# tc_breakout.net
KiCad netlist of a schematic drawn in EAGLE
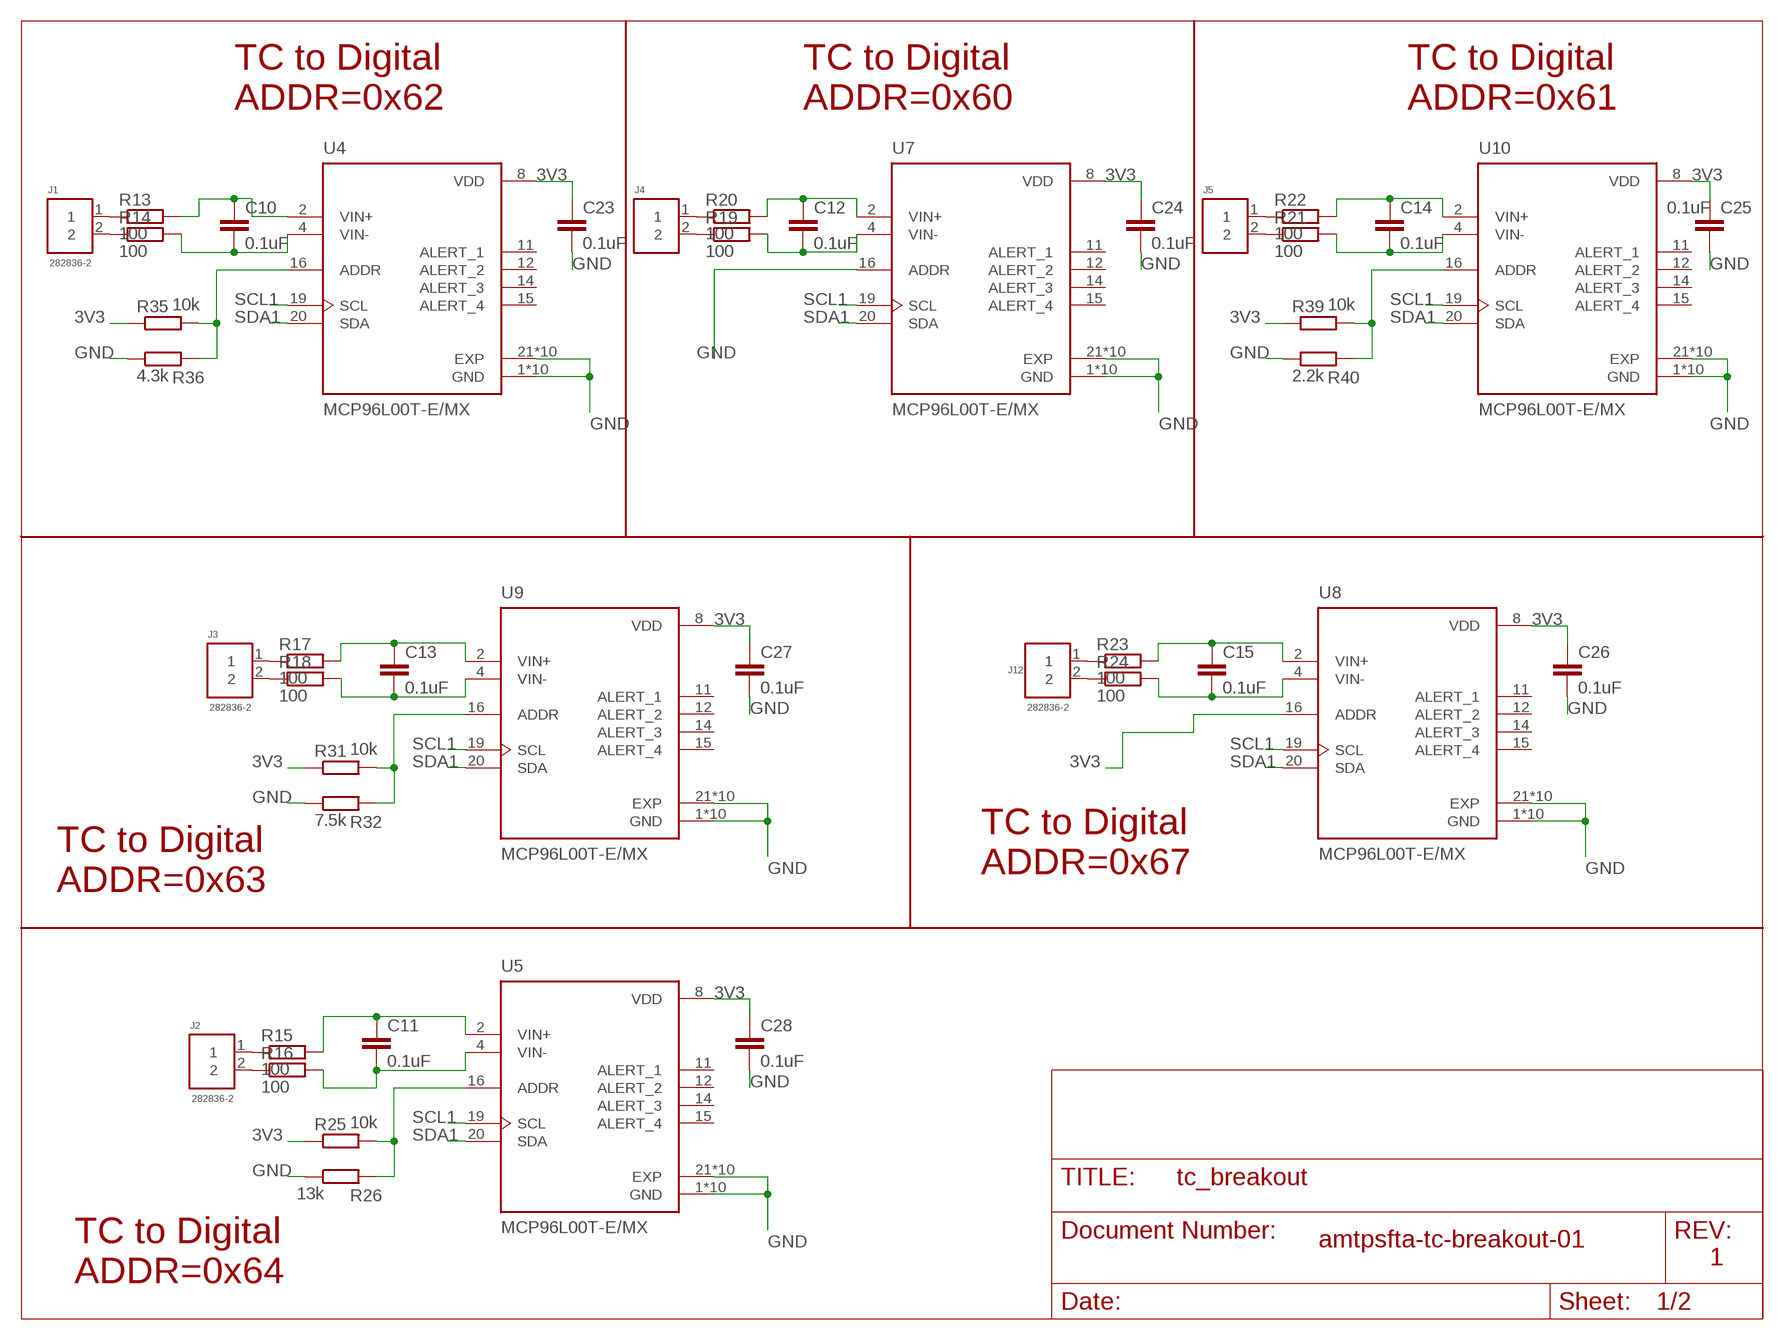
[diagram p0: schematic, sheet 1]
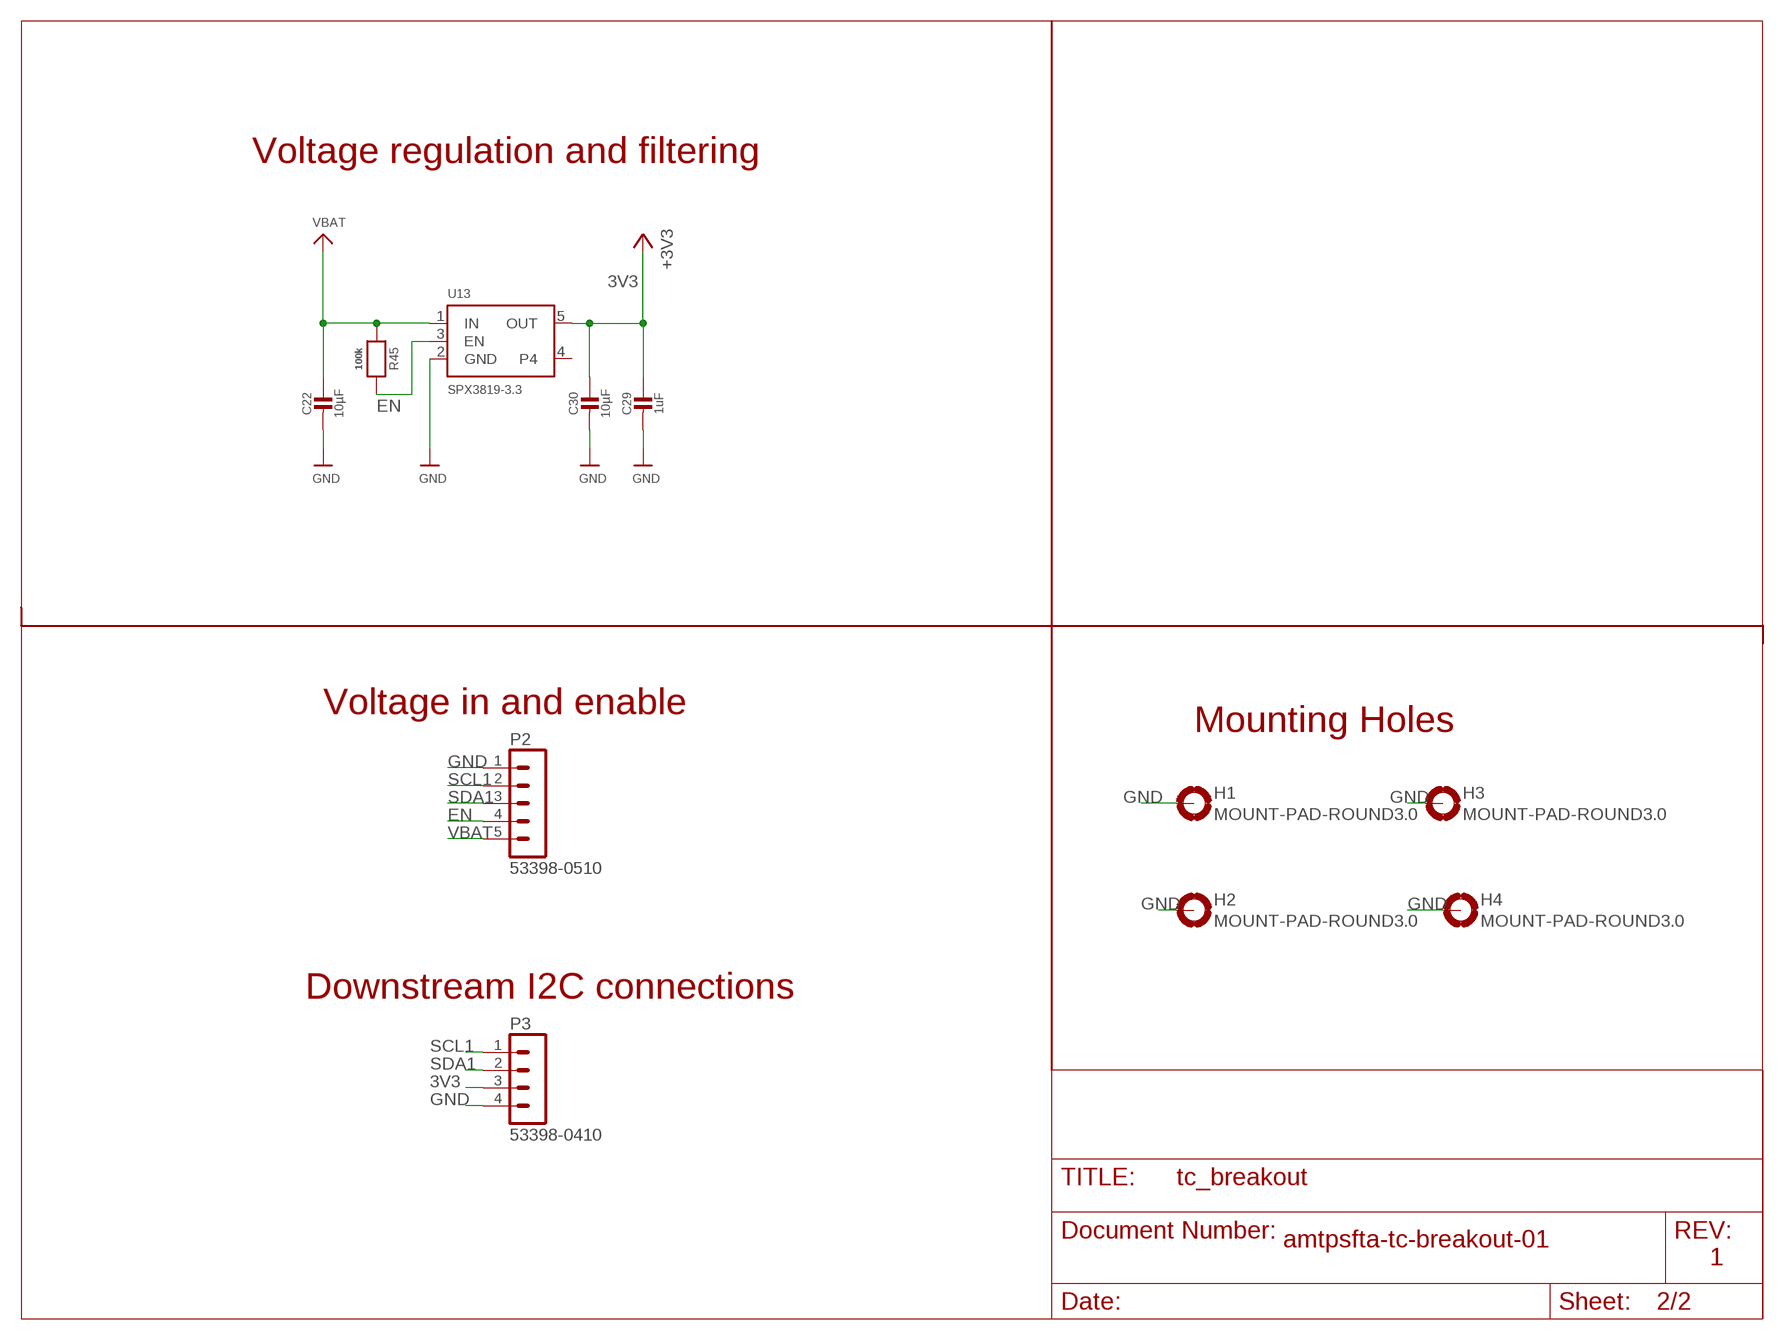
[diagram p1: schematic, sheet 2]

(export (version "E")
  (design (tool "Eeschema 10.0.6"))
  (components
    (comp (ref "C22")
      (value "10µF")
      (footprint "eagle-import:0805-NO")
      (libsource (lib "eagle-import") (part "CAP_CERAMIC0805-NOOUTLINE"))
    )
    (comp (ref "C29")
      (value "1uF")
      (footprint "eagle-import:0603-NO")
      (libsource (lib "eagle-import") (part "CAP_CERAMIC0603_NO"))
    )
    (comp (ref "C30")
      (value "10µF")
      (footprint "eagle-import:0805-NO")
      (libsource (lib "eagle-import") (part "CAP_CERAMIC0805-NOOUTLINE"))
    )
    (comp (ref "H1")
      (value "MOUNT-PAD-ROUND3.0")
      (footprint "eagle-import:3,0-PAD")
      (libsource (lib "eagle-import") (part "MOUNT-PAD-ROUND3.0"))
    )
    (comp (ref "H2")
      (value "MOUNT-PAD-ROUND3.0")
      (footprint "eagle-import:3,0-PAD")
      (libsource (lib "eagle-import") (part "MOUNT-PAD-ROUND3.0"))
    )
    (comp (ref "H3")
      (value "MOUNT-PAD-ROUND3.0")
      (footprint "eagle-import:3,0-PAD")
      (libsource (lib "eagle-import") (part "MOUNT-PAD-ROUND3.0"))
    )
    (comp (ref "H4")
      (value "MOUNT-PAD-ROUND3.0")
      (footprint "eagle-import:3,0-PAD")
      (libsource (lib "eagle-import") (part "MOUNT-PAD-ROUND3.0"))
    )
    (comp (ref "P2")
      (value "53398-0510")
      (footprint "eagle-import:53398-0510")
      (libsource (lib "eagle-import") (part "53398-0510"))
    )
    (comp (ref "P3")
      (value "53398-0410")
      (footprint "eagle-import:53398-0410")
      (libsource (lib "eagle-import") (part "53398-0410"))
    )
    (comp (ref "R45")
      (value "100k")
      (footprint "eagle-import:0603-NO")
      (libsource (lib "eagle-import") (part "RESISTOR_0603_NOOUT"))
    )
    (comp (ref "U13")
      (value "SPX3819-3.3")
      (footprint "eagle-import:SOT23-5")
      (libsource (lib "eagle-import") (part "VREG_SOT23-5"))
    )
    (comp (ref "C10")
      (value "0.1uF")
      (footprint "eagle-import:C0603")
      (libsource (lib "eagle-import") (part "C-EUC0603"))
    )
    (comp (ref "C11")
      (value "0.1uF")
      (footprint "eagle-import:C0603")
      (libsource (lib "eagle-import") (part "C-EUC0603"))
    )
    (comp (ref "C12")
      (value "0.1uF")
      (footprint "eagle-import:C0603")
      (libsource (lib "eagle-import") (part "C-EUC0603"))
    )
    (comp (ref "C13")
      (value "0.1uF")
      (footprint "eagle-import:C0603")
      (libsource (lib "eagle-import") (part "C-EUC0603"))
    )
    (comp (ref "C14")
      (value "0.1uF")
      (footprint "eagle-import:C0603")
      (libsource (lib "eagle-import") (part "C-EUC0603"))
    )
    (comp (ref "C15")
      (value "0.1uF")
      (footprint "eagle-import:C0603")
      (libsource (lib "eagle-import") (part "C-EUC0603"))
    )
    (comp (ref "C23")
      (value "0.1uF")
      (footprint "eagle-import:C0603")
      (libsource (lib "eagle-import") (part "C-EUC0603"))
    )
    (comp (ref "C24")
      (value "0.1uF")
      (footprint "eagle-import:C0603")
      (libsource (lib "eagle-import") (part "C-EUC0603"))
    )
    (comp (ref "C25")
      (value "0.1uF")
      (footprint "eagle-import:C0603")
      (libsource (lib "eagle-import") (part "C-EUC0603"))
    )
    (comp (ref "C26")
      (value "0.1uF")
      (footprint "eagle-import:C0603")
      (libsource (lib "eagle-import") (part "C-EUC0603"))
    )
    (comp (ref "C27")
      (value "0.1uF")
      (footprint "eagle-import:C0603")
      (libsource (lib "eagle-import") (part "C-EUC0603"))
    )
    (comp (ref "C28")
      (value "0.1uF")
      (footprint "eagle-import:C0603")
      (libsource (lib "eagle-import") (part "C-EUC0603"))
    )
    (comp (ref "J1")
      (value "282836-2")
      (footprint "eagle-import:CONN_282836-2")
      (fields (field (name "MF") "TE Connectivity") (field (name "MP") "2828362"))
      (libsource (lib "eagle-import") (part "282836-2"))
    )
    (comp (ref "J2")
      (value "282836-2")
      (footprint "eagle-import:CONN_282836-2")
      (fields (field (name "MF") "TE Connectivity") (field (name "MP") "2828362"))
      (libsource (lib "eagle-import") (part "282836-2"))
    )
    (comp (ref "J3")
      (value "282836-2")
      (footprint "eagle-import:CONN_282836-2")
      (fields (field (name "MF") "TE Connectivity") (field (name "MP") "2828362"))
      (libsource (lib "eagle-import") (part "282836-2"))
    )
    (comp (ref "J4")
      (value "282836-2")
      (footprint "eagle-import:CONN_282836-2")
      (fields (field (name "MF") "TE Connectivity") (field (name "MP") "2828362"))
      (libsource (lib "eagle-import") (part "282836-2"))
    )
    (comp (ref "J5")
      (value "282836-2")
      (footprint "eagle-import:CONN_282836-2")
      (fields (field (name "MF") "TE Connectivity") (field (name "MP") "2828362"))
      (libsource (lib "eagle-import") (part "282836-2"))
    )
    (comp (ref "J12")
      (value "282836-2")
      (footprint "eagle-import:CONN_282836-2")
      (fields (field (name "MF") "TE Connectivity") (field (name "MP") "2828362"))
      (libsource (lib "eagle-import") (part "282836-2"))
    )
    (comp (ref "R13")
      (value "100")
      (footprint "eagle-import:R0603")
      (libsource (lib "eagle-import") (part "R-EU_R0603"))
    )
    (comp (ref "R14")
      (value "100")
      (footprint "eagle-import:R0603")
      (libsource (lib "eagle-import") (part "R-EU_R0603"))
    )
    (comp (ref "R15")
      (value "100")
      (footprint "eagle-import:R0603")
      (libsource (lib "eagle-import") (part "R-EU_R0603"))
    )
    (comp (ref "R16")
      (value "100")
      (footprint "eagle-import:R0603")
      (libsource (lib "eagle-import") (part "R-EU_R0603"))
    )
    (comp (ref "R17")
      (value "100")
      (footprint "eagle-import:R0603")
      (libsource (lib "eagle-import") (part "R-EU_R0603"))
    )
    (comp (ref "R18")
      (value "100")
      (footprint "eagle-import:R0603")
      (libsource (lib "eagle-import") (part "R-EU_R0603"))
    )
    (comp (ref "R19")
      (value "100")
      (footprint "eagle-import:R0603")
      (libsource (lib "eagle-import") (part "R-EU_R0603"))
    )
    (comp (ref "R20")
      (value "100")
      (footprint "eagle-import:R0603")
      (libsource (lib "eagle-import") (part "R-EU_R0603"))
    )
    (comp (ref "R21")
      (value "100")
      (footprint "eagle-import:R0603")
      (libsource (lib "eagle-import") (part "R-EU_R0603"))
    )
    (comp (ref "R22")
      (value "100")
      (footprint "eagle-import:R0603")
      (libsource (lib "eagle-import") (part "R-EU_R0603"))
    )
    (comp (ref "R23")
      (value "100")
      (footprint "eagle-import:R0603")
      (libsource (lib "eagle-import") (part "R-EU_R0603"))
    )
    (comp (ref "R24")
      (value "100")
      (footprint "eagle-import:R0603")
      (libsource (lib "eagle-import") (part "R-EU_R0603"))
    )
    (comp (ref "R25")
      (value "10k")
      (footprint "eagle-import:R0603")
      (libsource (lib "eagle-import") (part "R-EU_R0603"))
    )
    (comp (ref "R26")
      (value "13k")
      (footprint "eagle-import:R0603")
      (libsource (lib "eagle-import") (part "R-EU_R0603"))
    )
    (comp (ref "R31")
      (value "10k")
      (footprint "eagle-import:R0603")
      (libsource (lib "eagle-import") (part "R-EU_R0603"))
    )
    (comp (ref "R32")
      (value "7.5k")
      (footprint "eagle-import:R0603")
      (libsource (lib "eagle-import") (part "R-EU_R0603"))
    )
    (comp (ref "R35")
      (value "10k")
      (footprint "eagle-import:R0603")
      (libsource (lib "eagle-import") (part "R-EU_R0603"))
    )
    (comp (ref "R36")
      (value "4.3k")
      (footprint "eagle-import:R0603")
      (libsource (lib "eagle-import") (part "R-EU_R0603"))
    )
    (comp (ref "R39")
      (value "10k")
      (footprint "eagle-import:R0603")
      (libsource (lib "eagle-import") (part "R-EU_R0603"))
    )
    (comp (ref "R40")
      (value "2.2k")
      (footprint "eagle-import:R0603")
      (libsource (lib "eagle-import") (part "R-EU_R0603"))
    )
    (comp (ref "U4")
      (value "MCP96L00T-E/MX")
      (footprint "eagle-import:QFN65P500X500X100-21N_MCP96L00T-E_MX")
      (fields
        (field (name "DIGI-KEY_PART_NUMBER") "MCP96L00T-E/MXCT-ND")
        (field (name "MF") "Microchip Technology")
      )
      (libsource (lib "eagle-import") (part "MCP96L00T-E/MX"))
    )
    (comp (ref "U5")
      (value "MCP96L00T-E/MX")
      (footprint "eagle-import:QFN65P500X500X100-21N_MCP96L00T-E_MX")
      (fields
        (field (name "DIGI-KEY_PART_NUMBER") "MCP96L00T-E/MXCT-ND")
        (field (name "MF") "Microchip Technology")
      )
      (libsource (lib "eagle-import") (part "MCP96L00T-E/MX"))
    )
    (comp (ref "U7")
      (value "MCP96L00T-E/MX")
      (footprint "eagle-import:QFN65P500X500X100-21N_MCP96L00T-E_MX")
      (fields
        (field (name "DIGI-KEY_PART_NUMBER") "MCP96L00T-E/MXCT-ND")
        (field (name "MF") "Microchip Technology")
      )
      (libsource (lib "eagle-import") (part "MCP96L00T-E/MX"))
    )
    (comp (ref "U8")
      (value "MCP96L00T-E/MX")
      (footprint "eagle-import:QFN65P500X500X100-21N_MCP96L00T-E_MX")
      (fields
        (field (name "DIGI-KEY_PART_NUMBER") "MCP96L00T-E/MXCT-ND")
        (field (name "MF") "Microchip Technology")
      )
      (libsource (lib "eagle-import") (part "MCP96L00T-E/MX"))
    )
    (comp (ref "U9")
      (value "MCP96L00T-E/MX")
      (footprint "eagle-import:QFN65P500X500X100-21N_MCP96L00T-E_MX")
      (fields
        (field (name "DIGI-KEY_PART_NUMBER") "MCP96L00T-E/MXCT-ND")
        (field (name "MF") "Microchip Technology")
      )
      (libsource (lib "eagle-import") (part "MCP96L00T-E/MX"))
    )
    (comp (ref "U10")
      (value "MCP96L00T-E/MX")
      (footprint "eagle-import:QFN65P500X500X100-21N_MCP96L00T-E_MX")
      (fields
        (field (name "DIGI-KEY_PART_NUMBER") "MCP96L00T-E/MXCT-ND")
        (field (name "MF") "Microchip Technology")
      )
      (libsource (lib "eagle-import") (part "MCP96L00T-E/MX"))
    )
  )
  (nets
    (net (code "1") (name "3V3") (class "Default")
      (node (ref "C23") (pin "1") (pinfunction "1_1") (pintype "passive"))
      (node (ref "C24") (pin "1") (pinfunction "1_1") (pintype "passive"))
      (node (ref "C25") (pin "1") (pinfunction "1_1") (pintype "passive"))
      (node (ref "C26") (pin "1") (pinfunction "1_1") (pintype "passive"))
      (node (ref "C27") (pin "1") (pinfunction "1_1") (pintype "passive"))
      (node (ref "C28") (pin "1") (pinfunction "1_1") (pintype "passive"))
      (node (ref "C29") (pin "1") (pinfunction "1_1") (pintype "passive"))
      (node (ref "C30") (pin "1") (pinfunction "1_1") (pintype "passive"))
      (node (ref "P3") (pin "3") (pinfunction "3_3") (pintype "passive"))
      (node (ref "R25") (pin "1") (pinfunction "1_1") (pintype "passive"))
      (node (ref "R31") (pin "1") (pinfunction "1_1") (pintype "passive"))
      (node (ref "R35") (pin "1") (pinfunction "1_1") (pintype "passive"))
      (node (ref "R39") (pin "1") (pinfunction "1_1") (pintype "passive"))
      (node (ref "U10") (pin "8") (pinfunction "VDD_8") (pintype "power_in"))
      (node (ref "U13") (pin "5") (pinfunction "OUT_5") (pintype "power_in"))
      (node (ref "U4") (pin "8") (pinfunction "VDD_8") (pintype "power_in"))
      (node (ref "U5") (pin "8") (pinfunction "VDD_8") (pintype "power_in"))
      (node (ref "U7") (pin "8") (pinfunction "VDD_8") (pintype "power_in"))
      (node (ref "U8") (pin "16") (pinfunction "ADDR_16") (pintype "input"))
      (node (ref "U8") (pin "8") (pinfunction "VDD_8") (pintype "power_in"))
      (node (ref "U9") (pin "8") (pinfunction "VDD_8") (pintype "power_in"))
    )
    (net (code "2") (name "EN") (class "Default")
      (node (ref "P2") (pin "4") (pinfunction "4_4") (pintype "passive"))
      (node (ref "R45") (pin "2") (pinfunction "2_2") (pintype "passive"))
      (node (ref "U13") (pin "3") (pinfunction "EN_3") (pintype "input"))
    )
    (net (code "3") (name "GND") (class "Default")
      (node (ref "C22") (pin "2") (pinfunction "2_2") (pintype "passive"))
      (node (ref "C23") (pin "2") (pinfunction "2_2") (pintype "passive"))
      (node (ref "C24") (pin "2") (pinfunction "2_2") (pintype "passive"))
      (node (ref "C25") (pin "2") (pinfunction "2_2") (pintype "passive"))
      (node (ref "C26") (pin "2") (pinfunction "2_2") (pintype "passive"))
      (node (ref "C27") (pin "2") (pinfunction "2_2") (pintype "passive"))
      (node (ref "C28") (pin "2") (pinfunction "2_2") (pintype "passive"))
      (node (ref "C29") (pin "2") (pinfunction "2_2") (pintype "passive"))
      (node (ref "C30") (pin "2") (pinfunction "2_2") (pintype "passive"))
      (node (ref "H1") (pin "B3,0") (pinfunction "MOUNT_B3,0") (pintype "passive"))
      (node (ref "H2") (pin "B3,0") (pinfunction "MOUNT_B3,0") (pintype "passive"))
      (node (ref "H3") (pin "B3,0") (pinfunction "MOUNT_B3,0") (pintype "passive"))
      (node (ref "H4") (pin "B3,0") (pinfunction "MOUNT_B3,0") (pintype "passive"))
      (node (ref "P2") (pin "1") (pinfunction "1_1") (pintype "passive"))
      (node (ref "P3") (pin "4") (pinfunction "4_4") (pintype "passive"))
      (node (ref "R26") (pin "1") (pinfunction "1_1") (pintype "passive"))
      (node (ref "R32") (pin "1") (pinfunction "1_1") (pintype "passive"))
      (node (ref "R36") (pin "1") (pinfunction "1_1") (pintype "passive"))
      (node (ref "R40") (pin "1") (pinfunction "1_1") (pintype "passive"))
      (node (ref "U10") (pin "1") (pinfunction "GND_1") (pintype "power_in"))
      (node (ref "U10") (pin "10") (pinfunction "GND_10") (pintype "power_in"))
      (node (ref "U10") (pin "13") (pinfunction "GND_13") (pintype "power_in"))
      (node (ref "U10") (pin "17") (pinfunction "GND_17") (pintype "power_in"))
      (node (ref "U10") (pin "18") (pinfunction "GND_18") (pintype "power_in"))
      (node (ref "U10") (pin "21") (pinfunction "EXP_21") (pintype "power_in"))
      (node (ref "U10") (pin "22") (pinfunction "EXP_22") (pintype "power_in"))
      (node (ref "U10") (pin "23") (pinfunction "EXP_23") (pintype "power_in"))
      (node (ref "U10") (pin "24") (pinfunction "EXP_24") (pintype "power_in"))
      (node (ref "U10") (pin "25") (pinfunction "EXP_25") (pintype "power_in"))
      (node (ref "U10") (pin "26") (pinfunction "EXP_26") (pintype "power_in"))
      (node (ref "U10") (pin "27") (pinfunction "EXP_27") (pintype "power_in"))
      (node (ref "U10") (pin "28") (pinfunction "EXP_28") (pintype "power_in"))
      (node (ref "U10") (pin "29") (pinfunction "EXP_29") (pintype "power_in"))
      (node (ref "U10") (pin "3") (pinfunction "GND_3") (pintype "power_in"))
      (node (ref "U10") (pin "30") (pinfunction "EXP_30") (pintype "power_in"))
      (node (ref "U10") (pin "5") (pinfunction "GND_5") (pintype "power_in"))
      (node (ref "U10") (pin "6") (pinfunction "GND_6") (pintype "power_in"))
      (node (ref "U10") (pin "7") (pinfunction "GND_7") (pintype "power_in"))
      (node (ref "U10") (pin "9") (pinfunction "GND_9") (pintype "power_in"))
      (node (ref "U13") (pin "2") (pinfunction "GND_2") (pintype "power_in"))
      (node (ref "U4") (pin "1") (pinfunction "GND_1") (pintype "power_in"))
      (node (ref "U4") (pin "10") (pinfunction "GND_10") (pintype "power_in"))
      (node (ref "U4") (pin "13") (pinfunction "GND_13") (pintype "power_in"))
      (node (ref "U4") (pin "17") (pinfunction "GND_17") (pintype "power_in"))
      (node (ref "U4") (pin "18") (pinfunction "GND_18") (pintype "power_in"))
      (node (ref "U4") (pin "21") (pinfunction "EXP_21") (pintype "power_in"))
      (node (ref "U4") (pin "22") (pinfunction "EXP_22") (pintype "power_in"))
      (node (ref "U4") (pin "23") (pinfunction "EXP_23") (pintype "power_in"))
      (node (ref "U4") (pin "24") (pinfunction "EXP_24") (pintype "power_in"))
      (node (ref "U4") (pin "25") (pinfunction "EXP_25") (pintype "power_in"))
      (node (ref "U4") (pin "26") (pinfunction "EXP_26") (pintype "power_in"))
      (node (ref "U4") (pin "27") (pinfunction "EXP_27") (pintype "power_in"))
      (node (ref "U4") (pin "28") (pinfunction "EXP_28") (pintype "power_in"))
      (node (ref "U4") (pin "29") (pinfunction "EXP_29") (pintype "power_in"))
      (node (ref "U4") (pin "3") (pinfunction "GND_3") (pintype "power_in"))
      (node (ref "U4") (pin "30") (pinfunction "EXP_30") (pintype "power_in"))
      (node (ref "U4") (pin "5") (pinfunction "GND_5") (pintype "power_in"))
      (node (ref "U4") (pin "6") (pinfunction "GND_6") (pintype "power_in"))
      (node (ref "U4") (pin "7") (pinfunction "GND_7") (pintype "power_in"))
      (node (ref "U4") (pin "9") (pinfunction "GND_9") (pintype "power_in"))
      (node (ref "U5") (pin "1") (pinfunction "GND_1") (pintype "power_in"))
      (node (ref "U5") (pin "10") (pinfunction "GND_10") (pintype "power_in"))
      (node (ref "U5") (pin "13") (pinfunction "GND_13") (pintype "power_in"))
      (node (ref "U5") (pin "17") (pinfunction "GND_17") (pintype "power_in"))
      (node (ref "U5") (pin "18") (pinfunction "GND_18") (pintype "power_in"))
      (node (ref "U5") (pin "21") (pinfunction "EXP_21") (pintype "power_in"))
      (node (ref "U5") (pin "22") (pinfunction "EXP_22") (pintype "power_in"))
      (node (ref "U5") (pin "23") (pinfunction "EXP_23") (pintype "power_in"))
      (node (ref "U5") (pin "24") (pinfunction "EXP_24") (pintype "power_in"))
      (node (ref "U5") (pin "25") (pinfunction "EXP_25") (pintype "power_in"))
      (node (ref "U5") (pin "26") (pinfunction "EXP_26") (pintype "power_in"))
      (node (ref "U5") (pin "27") (pinfunction "EXP_27") (pintype "power_in"))
      (node (ref "U5") (pin "28") (pinfunction "EXP_28") (pintype "power_in"))
      (node (ref "U5") (pin "29") (pinfunction "EXP_29") (pintype "power_in"))
      (node (ref "U5") (pin "3") (pinfunction "GND_3") (pintype "power_in"))
      (node (ref "U5") (pin "30") (pinfunction "EXP_30") (pintype "power_in"))
      (node (ref "U5") (pin "5") (pinfunction "GND_5") (pintype "power_in"))
      (node (ref "U5") (pin "6") (pinfunction "GND_6") (pintype "power_in"))
      (node (ref "U5") (pin "7") (pinfunction "GND_7") (pintype "power_in"))
      (node (ref "U5") (pin "9") (pinfunction "GND_9") (pintype "power_in"))
      (node (ref "U7") (pin "1") (pinfunction "GND_1") (pintype "power_in"))
      (node (ref "U7") (pin "10") (pinfunction "GND_10") (pintype "power_in"))
      (node (ref "U7") (pin "13") (pinfunction "GND_13") (pintype "power_in"))
      (node (ref "U7") (pin "16") (pinfunction "ADDR_16") (pintype "input"))
      (node (ref "U7") (pin "17") (pinfunction "GND_17") (pintype "power_in"))
      (node (ref "U7") (pin "18") (pinfunction "GND_18") (pintype "power_in"))
      (node (ref "U7") (pin "21") (pinfunction "EXP_21") (pintype "power_in"))
      (node (ref "U7") (pin "22") (pinfunction "EXP_22") (pintype "power_in"))
      (node (ref "U7") (pin "23") (pinfunction "EXP_23") (pintype "power_in"))
      (node (ref "U7") (pin "24") (pinfunction "EXP_24") (pintype "power_in"))
      (node (ref "U7") (pin "25") (pinfunction "EXP_25") (pintype "power_in"))
      (node (ref "U7") (pin "26") (pinfunction "EXP_26") (pintype "power_in"))
      (node (ref "U7") (pin "27") (pinfunction "EXP_27") (pintype "power_in"))
      (node (ref "U7") (pin "28") (pinfunction "EXP_28") (pintype "power_in"))
      (node (ref "U7") (pin "29") (pinfunction "EXP_29") (pintype "power_in"))
      (node (ref "U7") (pin "3") (pinfunction "GND_3") (pintype "power_in"))
      (node (ref "U7") (pin "30") (pinfunction "EXP_30") (pintype "power_in"))
      (node (ref "U7") (pin "5") (pinfunction "GND_5") (pintype "power_in"))
      (node (ref "U7") (pin "6") (pinfunction "GND_6") (pintype "power_in"))
      (node (ref "U7") (pin "7") (pinfunction "GND_7") (pintype "power_in"))
      (node (ref "U7") (pin "9") (pinfunction "GND_9") (pintype "power_in"))
      (node (ref "U8") (pin "1") (pinfunction "GND_1") (pintype "power_in"))
      (node (ref "U8") (pin "10") (pinfunction "GND_10") (pintype "power_in"))
      (node (ref "U8") (pin "13") (pinfunction "GND_13") (pintype "power_in"))
      (node (ref "U8") (pin "17") (pinfunction "GND_17") (pintype "power_in"))
      (node (ref "U8") (pin "18") (pinfunction "GND_18") (pintype "power_in"))
      (node (ref "U8") (pin "21") (pinfunction "EXP_21") (pintype "power_in"))
      (node (ref "U8") (pin "22") (pinfunction "EXP_22") (pintype "power_in"))
      (node (ref "U8") (pin "23") (pinfunction "EXP_23") (pintype "power_in"))
      (node (ref "U8") (pin "24") (pinfunction "EXP_24") (pintype "power_in"))
      (node (ref "U8") (pin "25") (pinfunction "EXP_25") (pintype "power_in"))
      (node (ref "U8") (pin "26") (pinfunction "EXP_26") (pintype "power_in"))
      (node (ref "U8") (pin "27") (pinfunction "EXP_27") (pintype "power_in"))
      (node (ref "U8") (pin "28") (pinfunction "EXP_28") (pintype "power_in"))
      (node (ref "U8") (pin "29") (pinfunction "EXP_29") (pintype "power_in"))
      (node (ref "U8") (pin "3") (pinfunction "GND_3") (pintype "power_in"))
      (node (ref "U8") (pin "30") (pinfunction "EXP_30") (pintype "power_in"))
      (node (ref "U8") (pin "5") (pinfunction "GND_5") (pintype "power_in"))
      (node (ref "U8") (pin "6") (pinfunction "GND_6") (pintype "power_in"))
      (node (ref "U8") (pin "7") (pinfunction "GND_7") (pintype "power_in"))
      (node (ref "U8") (pin "9") (pinfunction "GND_9") (pintype "power_in"))
      (node (ref "U9") (pin "1") (pinfunction "GND_1") (pintype "power_in"))
      (node (ref "U9") (pin "10") (pinfunction "GND_10") (pintype "power_in"))
      (node (ref "U9") (pin "13") (pinfunction "GND_13") (pintype "power_in"))
      (node (ref "U9") (pin "17") (pinfunction "GND_17") (pintype "power_in"))
      (node (ref "U9") (pin "18") (pinfunction "GND_18") (pintype "power_in"))
      (node (ref "U9") (pin "21") (pinfunction "EXP_21") (pintype "power_in"))
      (node (ref "U9") (pin "22") (pinfunction "EXP_22") (pintype "power_in"))
      (node (ref "U9") (pin "23") (pinfunction "EXP_23") (pintype "power_in"))
      (node (ref "U9") (pin "24") (pinfunction "EXP_24") (pintype "power_in"))
      (node (ref "U9") (pin "25") (pinfunction "EXP_25") (pintype "power_in"))
      (node (ref "U9") (pin "26") (pinfunction "EXP_26") (pintype "power_in"))
      (node (ref "U9") (pin "27") (pinfunction "EXP_27") (pintype "power_in"))
      (node (ref "U9") (pin "28") (pinfunction "EXP_28") (pintype "power_in"))
      (node (ref "U9") (pin "29") (pinfunction "EXP_29") (pintype "power_in"))
      (node (ref "U9") (pin "3") (pinfunction "GND_3") (pintype "power_in"))
      (node (ref "U9") (pin "30") (pinfunction "EXP_30") (pintype "power_in"))
      (node (ref "U9") (pin "5") (pinfunction "GND_5") (pintype "power_in"))
      (node (ref "U9") (pin "6") (pinfunction "GND_6") (pintype "power_in"))
      (node (ref "U9") (pin "7") (pinfunction "GND_7") (pintype "power_in"))
      (node (ref "U9") (pin "9") (pinfunction "GND_9") (pintype "power_in"))
    )
    (net (code "4") (name "Net-(J1-Pad1)") (class "Default")
      (node (ref "J1") (pin "1") (pinfunction "1_1") (pintype "passive"))
      (node (ref "R13") (pin "1") (pinfunction "1_1") (pintype "passive"))
    )
    (net (code "5") (name "Net-(J1-Pad2)") (class "Default")
      (node (ref "J1") (pin "2") (pinfunction "2_2") (pintype "passive"))
      (node (ref "R14") (pin "1") (pinfunction "1_1") (pintype "passive"))
    )
    (net (code "6") (name "Net-(J2-Pad1)") (class "Default")
      (node (ref "J2") (pin "1") (pinfunction "1_1") (pintype "passive"))
      (node (ref "R15") (pin "1") (pinfunction "1_1") (pintype "passive"))
    )
    (net (code "7") (name "Net-(J2-Pad2)") (class "Default")
      (node (ref "J2") (pin "2") (pinfunction "2_2") (pintype "passive"))
      (node (ref "R16") (pin "1") (pinfunction "1_1") (pintype "passive"))
    )
    (net (code "8") (name "Net-(J3-Pad1)") (class "Default")
      (node (ref "J3") (pin "1") (pinfunction "1_1") (pintype "passive"))
      (node (ref "R17") (pin "1") (pinfunction "1_1") (pintype "passive"))
    )
    (net (code "9") (name "Net-(J3-Pad2)") (class "Default")
      (node (ref "J3") (pin "2") (pinfunction "2_2") (pintype "passive"))
      (node (ref "R18") (pin "1") (pinfunction "1_1") (pintype "passive"))
    )
    (net (code "10") (name "Net-(J4-Pad1)") (class "Default")
      (node (ref "J4") (pin "1") (pinfunction "1_1") (pintype "passive"))
      (node (ref "R20") (pin "1") (pinfunction "1_1") (pintype "passive"))
    )
    (net (code "11") (name "Net-(J4-Pad2)") (class "Default")
      (node (ref "J4") (pin "2") (pinfunction "2_2") (pintype "passive"))
      (node (ref "R19") (pin "1") (pinfunction "1_1") (pintype "passive"))
    )
    (net (code "12") (name "Net-(J5-Pad1)") (class "Default")
      (node (ref "J5") (pin "1") (pinfunction "1_1") (pintype "passive"))
      (node (ref "R22") (pin "1") (pinfunction "1_1") (pintype "passive"))
    )
    (net (code "13") (name "Net-(J5-Pad2)") (class "Default")
      (node (ref "J5") (pin "2") (pinfunction "2_2") (pintype "passive"))
      (node (ref "R21") (pin "1") (pinfunction "1_1") (pintype "passive"))
    )
    (net (code "14") (name "Net-(J12-Pad1)") (class "Default")
      (node (ref "J12") (pin "1") (pinfunction "1_1") (pintype "passive"))
      (node (ref "R23") (pin "1") (pinfunction "1_1") (pintype "passive"))
    )
    (net (code "15") (name "Net-(J12-Pad2)") (class "Default")
      (node (ref "J12") (pin "2") (pinfunction "2_2") (pintype "passive"))
      (node (ref "R24") (pin "1") (pinfunction "1_1") (pintype "passive"))
    )
    (net (code "16") (name "Net-(U4-ADDR)") (class "Default")
      (node (ref "R35") (pin "2") (pinfunction "2_2") (pintype "passive"))
      (node (ref "R36") (pin "2") (pinfunction "2_2") (pintype "passive"))
      (node (ref "U4") (pin "16") (pinfunction "ADDR_16") (pintype "input"))
    )
    (net (code "17") (name "Net-(U4-VIN+)") (class "Default")
      (node (ref "C10") (pin "1") (pinfunction "1_1") (pintype "passive"))
      (node (ref "R13") (pin "2") (pinfunction "2_2") (pintype "passive"))
      (node (ref "U4") (pin "2") (pinfunction "VIN+_2") (pintype "input"))
    )
    (net (code "18") (name "Net-(U4-VIN-)") (class "Default")
      (node (ref "C10") (pin "2") (pinfunction "2_2") (pintype "passive"))
      (node (ref "R14") (pin "2") (pinfunction "2_2") (pintype "passive"))
      (node (ref "U4") (pin "4") (pinfunction "VIN-_4") (pintype "input"))
    )
    (net (code "19") (name "Net-(U5-ADDR)") (class "Default")
      (node (ref "R25") (pin "2") (pinfunction "2_2") (pintype "passive"))
      (node (ref "R26") (pin "2") (pinfunction "2_2") (pintype "passive"))
      (node (ref "U5") (pin "16") (pinfunction "ADDR_16") (pintype "input"))
    )
    (net (code "20") (name "Net-(U5-VIN+)") (class "Default")
      (node (ref "C11") (pin "1") (pinfunction "1_1") (pintype "passive"))
      (node (ref "R15") (pin "2") (pinfunction "2_2") (pintype "passive"))
      (node (ref "U5") (pin "2") (pinfunction "VIN+_2") (pintype "input"))
    )
    (net (code "21") (name "Net-(U5-VIN-)") (class "Default")
      (node (ref "C11") (pin "2") (pinfunction "2_2") (pintype "passive"))
      (node (ref "R16") (pin "2") (pinfunction "2_2") (pintype "passive"))
      (node (ref "U5") (pin "4") (pinfunction "VIN-_4") (pintype "input"))
    )
    (net (code "22") (name "Net-(U7-VIN+)") (class "Default")
      (node (ref "C12") (pin "1") (pinfunction "1_1") (pintype "passive"))
      (node (ref "R20") (pin "2") (pinfunction "2_2") (pintype "passive"))
      (node (ref "U7") (pin "2") (pinfunction "VIN+_2") (pintype "input"))
    )
    (net (code "23") (name "Net-(U7-VIN-)") (class "Default")
      (node (ref "C12") (pin "2") (pinfunction "2_2") (pintype "passive"))
      (node (ref "R19") (pin "2") (pinfunction "2_2") (pintype "passive"))
      (node (ref "U7") (pin "4") (pinfunction "VIN-_4") (pintype "input"))
    )
    (net (code "24") (name "Net-(U8-VIN+)") (class "Default")
      (node (ref "C15") (pin "1") (pinfunction "1_1") (pintype "passive"))
      (node (ref "R23") (pin "2") (pinfunction "2_2") (pintype "passive"))
      (node (ref "U8") (pin "2") (pinfunction "VIN+_2") (pintype "input"))
    )
    (net (code "25") (name "Net-(U8-VIN-)") (class "Default")
      (node (ref "C15") (pin "2") (pinfunction "2_2") (pintype "passive"))
      (node (ref "R24") (pin "2") (pinfunction "2_2") (pintype "passive"))
      (node (ref "U8") (pin "4") (pinfunction "VIN-_4") (pintype "input"))
    )
    (net (code "26") (name "Net-(U9-ADDR)") (class "Default")
      (node (ref "R31") (pin "2") (pinfunction "2_2") (pintype "passive"))
      (node (ref "R32") (pin "2") (pinfunction "2_2") (pintype "passive"))
      (node (ref "U9") (pin "16") (pinfunction "ADDR_16") (pintype "input"))
    )
    (net (code "27") (name "Net-(U9-VIN+)") (class "Default")
      (node (ref "C13") (pin "1") (pinfunction "1_1") (pintype "passive"))
      (node (ref "R17") (pin "2") (pinfunction "2_2") (pintype "passive"))
      (node (ref "U9") (pin "2") (pinfunction "VIN+_2") (pintype "input"))
    )
    (net (code "28") (name "Net-(U9-VIN-)") (class "Default")
      (node (ref "C13") (pin "2") (pinfunction "2_2") (pintype "passive"))
      (node (ref "R18") (pin "2") (pinfunction "2_2") (pintype "passive"))
      (node (ref "U9") (pin "4") (pinfunction "VIN-_4") (pintype "input"))
    )
    (net (code "29") (name "Net-(U10-ADDR)") (class "Default")
      (node (ref "R39") (pin "2") (pinfunction "2_2") (pintype "passive"))
      (node (ref "R40") (pin "2") (pinfunction "2_2") (pintype "passive"))
      (node (ref "U10") (pin "16") (pinfunction "ADDR_16") (pintype "input"))
    )
    (net (code "30") (name "Net-(U10-VIN+)") (class "Default")
      (node (ref "C14") (pin "1") (pinfunction "1_1") (pintype "passive"))
      (node (ref "R22") (pin "2") (pinfunction "2_2") (pintype "passive"))
      (node (ref "U10") (pin "2") (pinfunction "VIN+_2") (pintype "input"))
    )
    (net (code "31") (name "Net-(U10-VIN-)") (class "Default")
      (node (ref "C14") (pin "2") (pinfunction "2_2") (pintype "passive"))
      (node (ref "R21") (pin "2") (pinfunction "2_2") (pintype "passive"))
      (node (ref "U10") (pin "4") (pinfunction "VIN-_4") (pintype "input"))
    )
    (net (code "32") (name "SCL1") (class "Default")
      (node (ref "P2") (pin "2") (pinfunction "2_2") (pintype "passive"))
      (node (ref "P3") (pin "1") (pinfunction "1_1") (pintype "passive"))
      (node (ref "U10") (pin "19") (pinfunction "SCL_19") (pintype "input"))
      (node (ref "U4") (pin "19") (pinfunction "SCL_19") (pintype "input"))
      (node (ref "U5") (pin "19") (pinfunction "SCL_19") (pintype "input"))
      (node (ref "U7") (pin "19") (pinfunction "SCL_19") (pintype "input"))
      (node (ref "U8") (pin "19") (pinfunction "SCL_19") (pintype "input"))
      (node (ref "U9") (pin "19") (pinfunction "SCL_19") (pintype "input"))
    )
    (net (code "33") (name "SDA1") (class "Default")
      (node (ref "P2") (pin "3") (pinfunction "3_3") (pintype "passive"))
      (node (ref "P3") (pin "2") (pinfunction "2_2") (pintype "passive"))
      (node (ref "U10") (pin "20") (pinfunction "SDA_20") (pintype "bidirectional"))
      (node (ref "U4") (pin "20") (pinfunction "SDA_20") (pintype "bidirectional"))
      (node (ref "U5") (pin "20") (pinfunction "SDA_20") (pintype "bidirectional"))
      (node (ref "U7") (pin "20") (pinfunction "SDA_20") (pintype "bidirectional"))
      (node (ref "U8") (pin "20") (pinfunction "SDA_20") (pintype "bidirectional"))
      (node (ref "U9") (pin "20") (pinfunction "SDA_20") (pintype "bidirectional"))
    )
    (net (code "34") (name "VBAT") (class "Default")
      (node (ref "C22") (pin "1") (pinfunction "1_1") (pintype "passive"))
      (node (ref "P2") (pin "5") (pinfunction "5_5") (pintype "passive"))
      (node (ref "R45") (pin "1") (pinfunction "1_1") (pintype "passive"))
      (node (ref "U13") (pin "1") (pinfunction "IN_1") (pintype "power_in"))
    )
    (net (code "35") (name "unconnected-(U4-ALERT_1-Pad11)") (class "Default")
      (node (ref "U4") (pin "11") (pinfunction "ALERT_1_11") (pintype "output"))
    )
    (net (code "36") (name "unconnected-(U4-ALERT_2-Pad12)") (class "Default")
      (node (ref "U4") (pin "12") (pinfunction "ALERT_2_12") (pintype "output"))
    )
    (net (code "37") (name "unconnected-(U4-ALERT_3-Pad14)") (class "Default")
      (node (ref "U4") (pin "14") (pinfunction "ALERT_3_14") (pintype "output"))
    )
    (net (code "38") (name "unconnected-(U4-ALERT_4-Pad15)") (class "Default")
      (node (ref "U4") (pin "15") (pinfunction "ALERT_4_15") (pintype "output"))
    )
    (net (code "39") (name "unconnected-(U5-ALERT_1-Pad11)") (class "Default")
      (node (ref "U5") (pin "11") (pinfunction "ALERT_1_11") (pintype "output"))
    )
    (net (code "40") (name "unconnected-(U5-ALERT_2-Pad12)") (class "Default")
      (node (ref "U5") (pin "12") (pinfunction "ALERT_2_12") (pintype "output"))
    )
    (net (code "41") (name "unconnected-(U5-ALERT_3-Pad14)") (class "Default")
      (node (ref "U5") (pin "14") (pinfunction "ALERT_3_14") (pintype "output"))
    )
    (net (code "42") (name "unconnected-(U5-ALERT_4-Pad15)") (class "Default")
      (node (ref "U5") (pin "15") (pinfunction "ALERT_4_15") (pintype "output"))
    )
    (net (code "43") (name "unconnected-(U7-ALERT_1-Pad11)") (class "Default")
      (node (ref "U7") (pin "11") (pinfunction "ALERT_1_11") (pintype "output"))
    )
    (net (code "44") (name "unconnected-(U7-ALERT_2-Pad12)") (class "Default")
      (node (ref "U7") (pin "12") (pinfunction "ALERT_2_12") (pintype "output"))
    )
    (net (code "45") (name "unconnected-(U7-ALERT_3-Pad14)") (class "Default")
      (node (ref "U7") (pin "14") (pinfunction "ALERT_3_14") (pintype "output"))
    )
    (net (code "46") (name "unconnected-(U7-ALERT_4-Pad15)") (class "Default")
      (node (ref "U7") (pin "15") (pinfunction "ALERT_4_15") (pintype "output"))
    )
    (net (code "47") (name "unconnected-(U8-ALERT_1-Pad11)") (class "Default")
      (node (ref "U8") (pin "11") (pinfunction "ALERT_1_11") (pintype "output"))
    )
    (net (code "48") (name "unconnected-(U8-ALERT_2-Pad12)") (class "Default")
      (node (ref "U8") (pin "12") (pinfunction "ALERT_2_12") (pintype "output"))
    )
    (net (code "49") (name "unconnected-(U8-ALERT_3-Pad14)") (class "Default")
      (node (ref "U8") (pin "14") (pinfunction "ALERT_3_14") (pintype "output"))
    )
    (net (code "50") (name "unconnected-(U8-ALERT_4-Pad15)") (class "Default")
      (node (ref "U8") (pin "15") (pinfunction "ALERT_4_15") (pintype "output"))
    )
    (net (code "51") (name "unconnected-(U9-ALERT_1-Pad11)") (class "Default")
      (node (ref "U9") (pin "11") (pinfunction "ALERT_1_11") (pintype "output"))
    )
    (net (code "52") (name "unconnected-(U9-ALERT_2-Pad12)") (class "Default")
      (node (ref "U9") (pin "12") (pinfunction "ALERT_2_12") (pintype "output"))
    )
    (net (code "53") (name "unconnected-(U9-ALERT_3-Pad14)") (class "Default")
      (node (ref "U9") (pin "14") (pinfunction "ALERT_3_14") (pintype "output"))
    )
    (net (code "54") (name "unconnected-(U9-ALERT_4-Pad15)") (class "Default")
      (node (ref "U9") (pin "15") (pinfunction "ALERT_4_15") (pintype "output"))
    )
    (net (code "55") (name "unconnected-(U10-ALERT_1-Pad11)") (class "Default")
      (node (ref "U10") (pin "11") (pinfunction "ALERT_1_11") (pintype "output"))
    )
    (net (code "56") (name "unconnected-(U10-ALERT_2-Pad12)") (class "Default")
      (node (ref "U10") (pin "12") (pinfunction "ALERT_2_12") (pintype "output"))
    )
    (net (code "57") (name "unconnected-(U10-ALERT_3-Pad14)") (class "Default")
      (node (ref "U10") (pin "14") (pinfunction "ALERT_3_14") (pintype "output"))
    )
    (net (code "58") (name "unconnected-(U10-ALERT_4-Pad15)") (class "Default")
      (node (ref "U10") (pin "15") (pinfunction "ALERT_4_15") (pintype "output"))
    )
    (net (code "59") (name "unconnected-(U13-P4-Pad4)") (class "Default")
      (node (ref "U13") (pin "4") (pinfunction "P4_4") (pintype "bidirectional"))
    )
  )
)
